# controller_diods_lcd.net
KiCad netlist of a schematic drawn in EAGLE
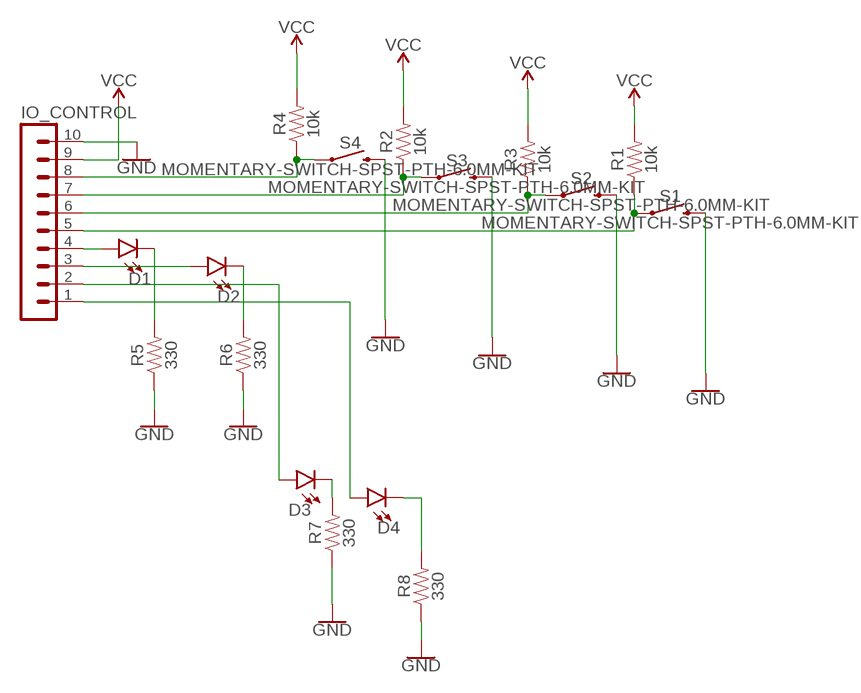
[diagram p0: schematic, sheet 1]

(export (version "E")
  (design (tool "Eeschema 10.0.6"))
  (components
    (comp (ref "D1")
      (value "LED10MM")
      (footprint "eagle-import:LED_10MM")
      (libsource (lib "eagle-import") (part "LED10MM"))
    )
    (comp (ref "D2")
      (value "LED10MM")
      (footprint "eagle-import:LED_10MM")
      (libsource (lib "eagle-import") (part "LED10MM"))
    )
    (comp (ref "D3")
      (value "LED10MM")
      (footprint "eagle-import:LED_10MM")
      (libsource (lib "eagle-import") (part "LED10MM"))
    )
    (comp (ref "D4")
      (value "LED10MM")
      (footprint "eagle-import:LED_10MM")
      (libsource (lib "eagle-import") (part "LED10MM"))
    )
    (comp (ref "IO_CONTROL")
      (value "MA10-1")
      (footprint "eagle-import:MA10-1")
      (libsource (lib "eagle-import") (part "MA10-1"))
    )
    (comp (ref "R1")
      (value "10k")
      (footprint "eagle-import:AXIAL-0.3-KIT")
      (libsource (lib "eagle-import") (part "10KOHM-HORIZ_KIT-1/6W-5%"))
    )
    (comp (ref "R2")
      (value "10k")
      (footprint "eagle-import:AXIAL-0.3-KIT")
      (libsource (lib "eagle-import") (part "10KOHM-HORIZ_KIT-1/6W-5%"))
    )
    (comp (ref "R3")
      (value "10k")
      (footprint "eagle-import:AXIAL-0.3-KIT")
      (libsource (lib "eagle-import") (part "10KOHM-HORIZ_KIT-1/6W-5%"))
    )
    (comp (ref "R4")
      (value "10k")
      (footprint "eagle-import:AXIAL-0.3-KIT")
      (libsource (lib "eagle-import") (part "10KOHM-HORIZ_KIT-1/6W-5%"))
    )
    (comp (ref "R5")
      (value "330")
      (footprint "eagle-import:AXIAL-0.3")
      (libsource (lib "eagle-import") (part "330OHM-HORIZ-1/10W-5%"))
    )
    (comp (ref "R6")
      (value "330")
      (footprint "eagle-import:AXIAL-0.3")
      (libsource (lib "eagle-import") (part "330OHM-HORIZ-1/10W-5%"))
    )
    (comp (ref "R7")
      (value "330")
      (footprint "eagle-import:AXIAL-0.3")
      (libsource (lib "eagle-import") (part "330OHM-HORIZ-1/10W-5%"))
    )
    (comp (ref "R8")
      (value "330")
      (footprint "eagle-import:AXIAL-0.3")
      (libsource (lib "eagle-import") (part "330OHM-HORIZ-1/10W-5%"))
    )
    (comp (ref "S1")
      (value "MOMENTARY-SWITCH-SPST-PTH-6.0MM-KIT")
      (footprint "eagle-import:TACTILE_SWITCH_PTH_6.0MM_KIT")
      (libsource (lib "eagle-import") (part "MOMENTARY-SWITCH-SPST-PTH-6.0MM-KIT"))
    )
    (comp (ref "S2")
      (value "MOMENTARY-SWITCH-SPST-PTH-6.0MM-KIT")
      (footprint "eagle-import:TACTILE_SWITCH_PTH_6.0MM_KIT")
      (libsource (lib "eagle-import") (part "MOMENTARY-SWITCH-SPST-PTH-6.0MM-KIT"))
    )
    (comp (ref "S3")
      (value "MOMENTARY-SWITCH-SPST-PTH-6.0MM-KIT")
      (footprint "eagle-import:TACTILE_SWITCH_PTH_6.0MM_KIT")
      (libsource (lib "eagle-import") (part "MOMENTARY-SWITCH-SPST-PTH-6.0MM-KIT"))
    )
    (comp (ref "S4")
      (value "MOMENTARY-SWITCH-SPST-PTH-6.0MM-KIT")
      (footprint "eagle-import:TACTILE_SWITCH_PTH_6.0MM_KIT")
      (libsource (lib "eagle-import") (part "MOMENTARY-SWITCH-SPST-PTH-6.0MM-KIT"))
    )
  )
  (nets
    (net (code "1") (name "GND") (class "Default")
      (node (ref "IO_CONTROL") (pin "10") (pinfunction "10_10") (pintype "passive"))
      (node (ref "R5") (pin "P$1") (pinfunction "1_P$1") (pintype "passive"))
      (node (ref "R6") (pin "P$1") (pinfunction "1_P$1") (pintype "passive"))
      (node (ref "R7") (pin "P$1") (pinfunction "1_P$1") (pintype "passive"))
      (node (ref "R8") (pin "P$1") (pinfunction "1_P$1") (pintype "passive"))
      (node (ref "S1") (pin "3") (pinfunction "2_3") (pintype "passive"))
      (node (ref "S2") (pin "3") (pinfunction "2_3") (pintype "passive"))
      (node (ref "S3") (pin "3") (pinfunction "2_3") (pintype "passive"))
      (node (ref "S4") (pin "3") (pinfunction "2_3") (pintype "passive"))
    )
    (net (code "2") (name "Net-(D1-PadA)") (class "Default")
      (node (ref "D1") (pin "A") (pinfunction "A_A") (pintype "passive"))
      (node (ref "IO_CONTROL") (pin "4") (pinfunction "4_4") (pintype "passive"))
    )
    (net (code "3") (name "Net-(D2-PadA)") (class "Default")
      (node (ref "D2") (pin "A") (pinfunction "A_A") (pintype "passive"))
      (node (ref "IO_CONTROL") (pin "3") (pinfunction "3_3") (pintype "passive"))
    )
    (net (code "4") (name "Net-(D3-PadA)") (class "Default")
      (node (ref "D3") (pin "A") (pinfunction "A_A") (pintype "passive"))
      (node (ref "IO_CONTROL") (pin "2") (pinfunction "2_2") (pintype "passive"))
    )
    (net (code "5") (name "Net-(D4-PadA)") (class "Default")
      (node (ref "D4") (pin "A") (pinfunction "A_A") (pintype "passive"))
      (node (ref "IO_CONTROL") (pin "1") (pinfunction "1_1") (pintype "passive"))
    )
    (net (code "6") (name "Net-(R1-1)") (class "Default")
      (node (ref "IO_CONTROL") (pin "5") (pinfunction "5_5") (pintype "passive"))
      (node (ref "R1") (pin "P$1") (pinfunction "1_P$1") (pintype "passive"))
      (node (ref "S1") (pin "1") (pinfunction "1_1") (pintype "passive"))
    )
    (net (code "7") (name "Net-(R2-1)") (class "Default")
      (node (ref "IO_CONTROL") (pin "7") (pinfunction "7_7") (pintype "passive"))
      (node (ref "R2") (pin "P$1") (pinfunction "1_P$1") (pintype "passive"))
      (node (ref "S3") (pin "1") (pinfunction "1_1") (pintype "passive"))
    )
    (net (code "8") (name "Net-(R3-1)") (class "Default")
      (node (ref "IO_CONTROL") (pin "6") (pinfunction "6_6") (pintype "passive"))
      (node (ref "R3") (pin "P$1") (pinfunction "1_P$1") (pintype "passive"))
      (node (ref "S2") (pin "1") (pinfunction "1_1") (pintype "passive"))
    )
    (net (code "9") (name "Net-(R4-1)") (class "Default")
      (node (ref "IO_CONTROL") (pin "8") (pinfunction "8_8") (pintype "passive"))
      (node (ref "R4") (pin "P$1") (pinfunction "1_P$1") (pintype "passive"))
      (node (ref "S4") (pin "1") (pinfunction "1_1") (pintype "passive"))
    )
    (net (code "10") (name "Net-(R5-2)") (class "Default")
      (node (ref "D1") (pin "C") (pinfunction "C_C") (pintype "passive"))
      (node (ref "R5") (pin "P$2") (pinfunction "2_P$2") (pintype "passive"))
    )
    (net (code "11") (name "Net-(R6-2)") (class "Default")
      (node (ref "D2") (pin "C") (pinfunction "C_C") (pintype "passive"))
      (node (ref "R6") (pin "P$2") (pinfunction "2_P$2") (pintype "passive"))
    )
    (net (code "12") (name "Net-(R7-2)") (class "Default")
      (node (ref "D3") (pin "C") (pinfunction "C_C") (pintype "passive"))
      (node (ref "R7") (pin "P$2") (pinfunction "2_P$2") (pintype "passive"))
    )
    (net (code "13") (name "Net-(R8-2)") (class "Default")
      (node (ref "D4") (pin "C") (pinfunction "C_C") (pintype "passive"))
      (node (ref "R8") (pin "P$2") (pinfunction "2_P$2") (pintype "passive"))
    )
    (net (code "14") (name "VCC") (class "Default")
      (node (ref "IO_CONTROL") (pin "9") (pinfunction "9_9") (pintype "passive"))
      (node (ref "R1") (pin "P$2") (pinfunction "2_P$2") (pintype "passive"))
      (node (ref "R2") (pin "P$2") (pinfunction "2_P$2") (pintype "passive"))
      (node (ref "R3") (pin "P$2") (pinfunction "2_P$2") (pintype "passive"))
      (node (ref "R4") (pin "P$2") (pinfunction "2_P$2") (pintype "passive"))
    )
  )
)
